# atx_power_control.net
KiCad netlist of a schematic drawn in EAGLE
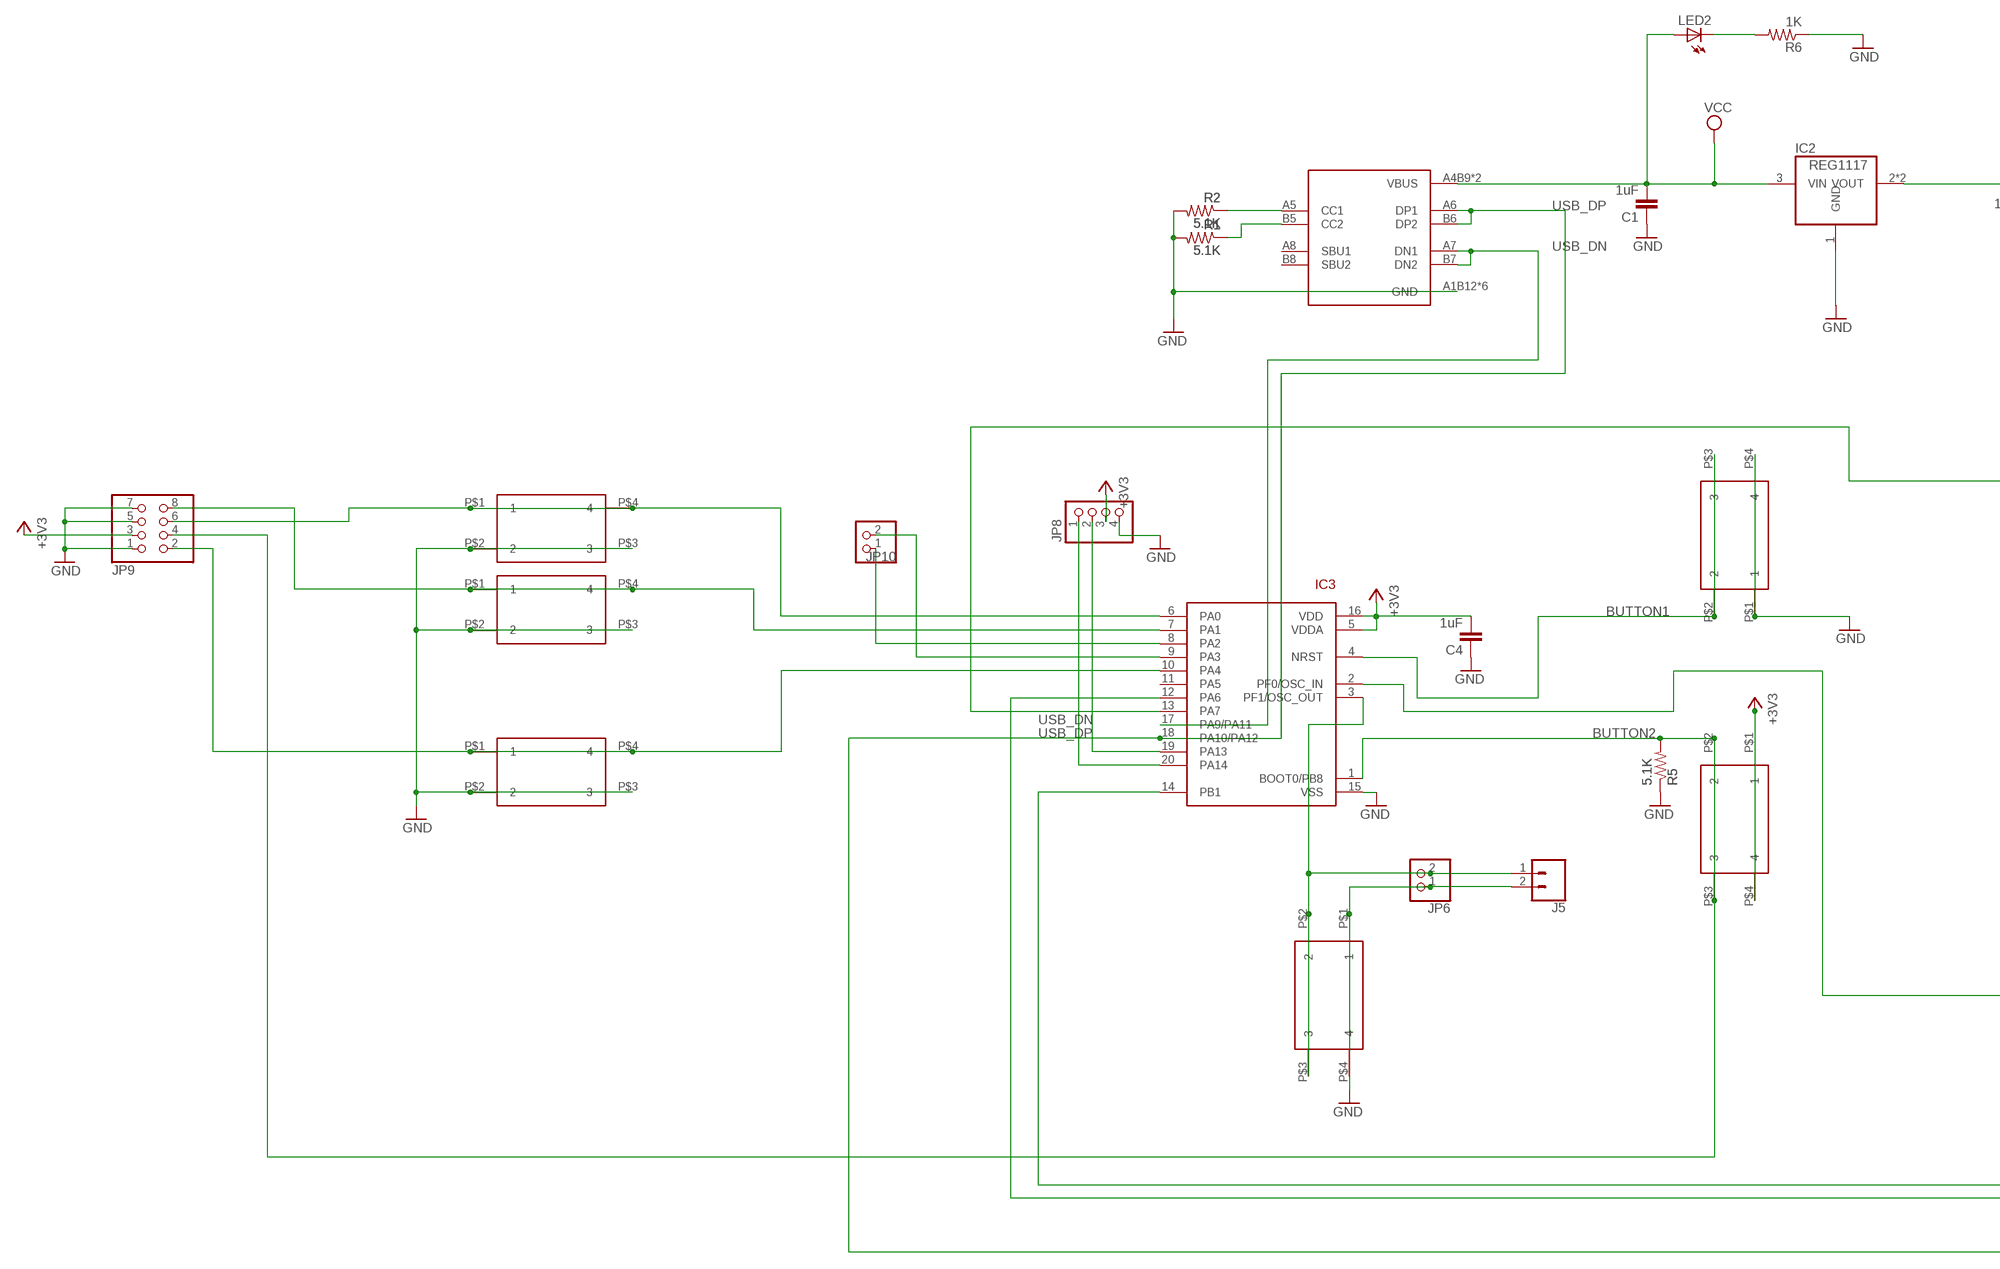
[diagram p0: schematic, sheet 1, part 1 of 2]
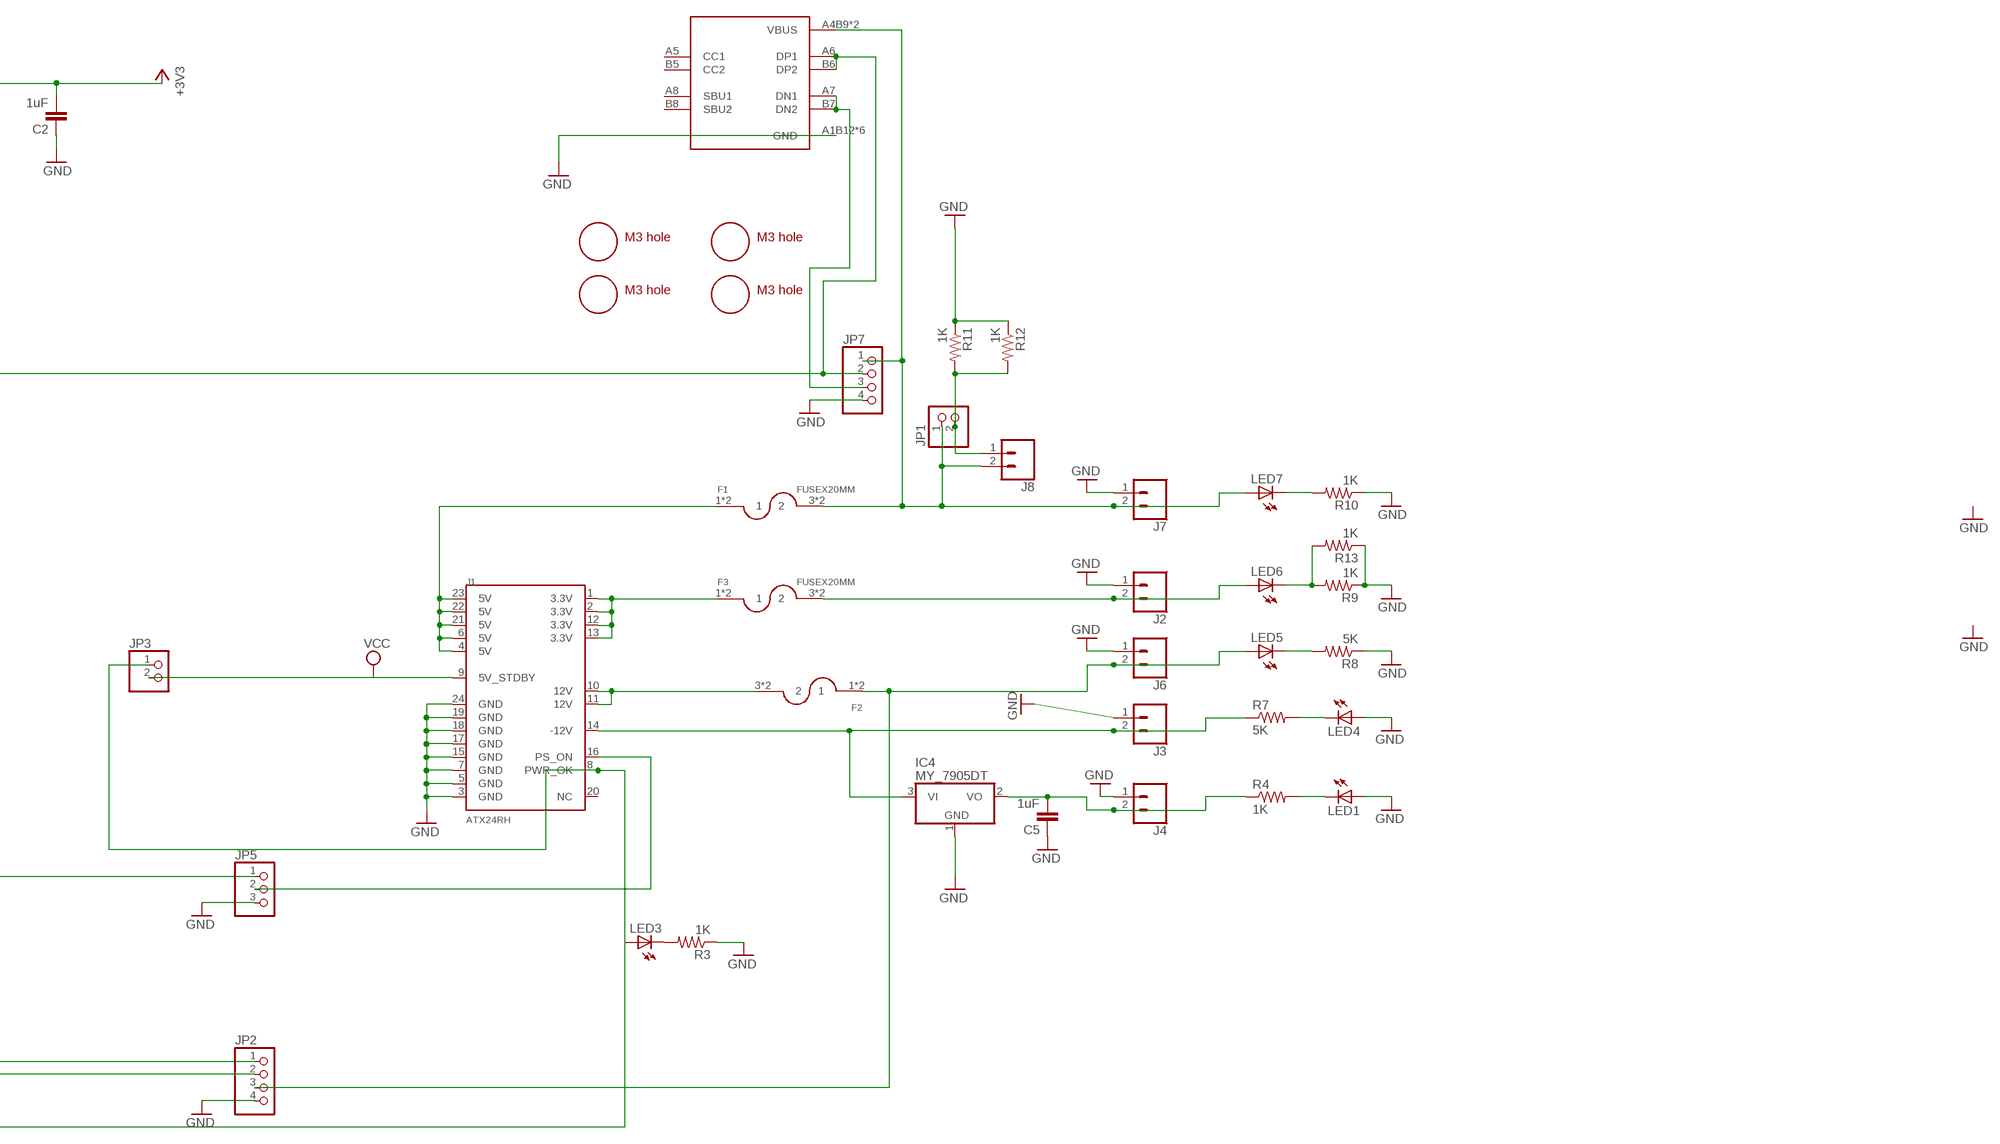
[diagram p1: schematic, sheet 1, part 2 of 2]

(export (version "E")
  (design (tool "Eeschema 10.0.6"))
  (components
    (comp (ref "C1")
      (value "1uF")
      (footprint "eagle-import:0805@1")
      (libsource (lib "eagle-import") (part "CAP0805"))
    )
    (comp (ref "C2")
      (value "1uF")
      (footprint "eagle-import:0805@1")
      (libsource (lib "eagle-import") (part "CAP0805"))
    )
    (comp (ref "C4")
      (value "1uF")
      (footprint "eagle-import:0805@1")
      (libsource (lib "eagle-import") (part "CAP0805"))
    )
    (comp (ref "C5")
      (value "1uF")
      (footprint "eagle-import:0805@1")
      (libsource (lib "eagle-import") (part "CAP0805"))
    )
    (comp (ref "F1")
      (value "FUSEX20MM")
      (footprint "eagle-import:FUSE_5MM")
      (libsource (lib "eagle-import") (part "FUSEX20MM"))
    )
    (comp (ref "F2")
      (value "FUSEX20MM")
      (footprint "eagle-import:FUSE_5MM")
      (libsource (lib "eagle-import") (part "FUSEX20MM"))
    )
    (comp (ref "F3")
      (value "FUSEX20MM")
      (footprint "eagle-import:FUSE_5MM")
      (libsource (lib "eagle-import") (part "FUSEX20MM"))
    )
    (comp (ref "IC2")
      (value "REG1117")
      (footprint "eagle-import:SOT223")
      (libsource (lib "eagle-import") (part "REG1117"))
    )
    (comp (ref "IC3")
      (value "STM32F042F4")
      (footprint "eagle-import:TSSOP20")
      (libsource (lib "eagle-import") (part "STM32F042F4"))
    )
    (comp (ref "IC4")
      (value "MY_7905DT")
      (footprint "eagle-import:ADAFRUIT_TO252")
      (libsource (lib "eagle-import") (part "MY_7905DT"))
    )
    (comp (ref "J1")
      (value "ATX24RH")
      (footprint "eagle-import:ATX24_RIGHT_ANGLE")
      (libsource (lib "eagle-import") (part "ATX24RH"))
    )
    (comp (ref "J2")
      (value "CONN_023.5MM")
      (footprint "eagle-import:SCREWTERMINAL-3.5MM-2")
      (libsource (lib "eagle-import") (part "CONN_023.5MM"))
    )
    (comp (ref "J3")
      (value "CONN_023.5MM")
      (footprint "eagle-import:SCREWTERMINAL-3.5MM-2")
      (libsource (lib "eagle-import") (part "CONN_023.5MM"))
    )
    (comp (ref "J4")
      (value "CONN_023.5MM")
      (footprint "eagle-import:SCREWTERMINAL-3.5MM-2")
      (libsource (lib "eagle-import") (part "CONN_023.5MM"))
    )
    (comp (ref "J5")
      (value "CONN_023.5MM")
      (footprint "eagle-import:SCREWTERMINAL-3.5MM-2")
      (libsource (lib "eagle-import") (part "CONN_023.5MM"))
    )
    (comp (ref "J6")
      (value "CONN_023.5MM")
      (footprint "eagle-import:SCREWTERMINAL-3.5MM-2")
      (libsource (lib "eagle-import") (part "CONN_023.5MM"))
    )
    (comp (ref "J7")
      (value "CONN_023.5MM-NO_SILK")
      (footprint "eagle-import:SCREWTERMINAL-3.5MM-2-NS")
      (libsource (lib "eagle-import") (part "CONN_023.5MM-NO_SILK"))
    )
    (comp (ref "J8")
      (value "CONN_023.5MM")
      (footprint "eagle-import:SCREWTERMINAL-3.5MM-2")
      (libsource (lib "eagle-import") (part "CONN_023.5MM"))
    )
    (comp (ref "JP1")
      (value "PINHD-1X2")
      (footprint "eagle-import:1X02")
      (libsource (lib "eagle-import") (part "PINHD-1X2"))
    )
    (comp (ref "JP2")
      (value "PINHD-1X4")
      (footprint "eagle-import:1X04")
      (libsource (lib "eagle-import") (part "PINHD-1X4"))
    )
    (comp (ref "JP3")
      (value "PINHD-1X2")
      (footprint "eagle-import:1X02")
      (libsource (lib "eagle-import") (part "PINHD-1X2"))
    )
    (comp (ref "JP5")
      (value "PINHD-1X3")
      (footprint "eagle-import:1X03")
      (libsource (lib "eagle-import") (part "PINHD-1X3"))
    )
    (comp (ref "JP6")
      (value "PINHD-1X2")
      (footprint "eagle-import:1X02")
      (libsource (lib "eagle-import") (part "PINHD-1X2"))
    )
    (comp (ref "JP7")
      (value "PINHD-1X4")
      (footprint "eagle-import:1X04")
      (libsource (lib "eagle-import") (part "PINHD-1X4"))
    )
    (comp (ref "JP8")
      (value "PINHD-1X4")
      (footprint "eagle-import:1X04")
      (libsource (lib "eagle-import") (part "PINHD-1X4"))
    )
    (comp (ref "JP9")
      (value "PINHD-2X4")
      (footprint "eagle-import:2X04")
      (libsource (lib "eagle-import") (part "PINHD-2X4"))
    )
    (comp (ref "JP10")
      (value "PINHD-1X2")
      (footprint "eagle-import:1X02")
      (libsource (lib "eagle-import") (part "PINHD-1X2"))
    )
    (comp (ref "LED1")
      (value "LEDCHIP-LED0805")
      (footprint "eagle-import:CHIP-LED0805")
      (libsource (lib "eagle-import") (part "LEDCHIP-LED0805"))
    )
    (comp (ref "LED2")
      (value "LEDCHIP-LED0805")
      (footprint "eagle-import:CHIP-LED0805")
      (libsource (lib "eagle-import") (part "LEDCHIP-LED0805"))
    )
    (comp (ref "LED3")
      (value "LEDCHIP-LED0805")
      (footprint "eagle-import:CHIP-LED0805")
      (libsource (lib "eagle-import") (part "LEDCHIP-LED0805"))
    )
    (comp (ref "LED4")
      (value "LEDCHIP-LED0805")
      (footprint "eagle-import:CHIP-LED0805")
      (libsource (lib "eagle-import") (part "LEDCHIP-LED0805"))
    )
    (comp (ref "LED5")
      (value "LEDCHIP-LED0805")
      (footprint "eagle-import:CHIP-LED0805")
      (libsource (lib "eagle-import") (part "LEDCHIP-LED0805"))
    )
    (comp (ref "LED6")
      (value "LEDCHIP-LED0805")
      (footprint "eagle-import:CHIP-LED0805")
      (libsource (lib "eagle-import") (part "LEDCHIP-LED0805"))
    )
    (comp (ref "LED7")
      (value "LEDCHIP-LED0805")
      (footprint "eagle-import:CHIP-LED0805")
      (libsource (lib "eagle-import") (part "LEDCHIP-LED0805"))
    )
    (comp (ref "R1")
      (value "5.1K")
      (footprint "eagle-import:0805")
      (libsource (lib "eagle-import") (part "joyAnalog_RESISTOR0805-RES"))
    )
    (comp (ref "R2")
      (value "5.1K")
      (footprint "eagle-import:0805")
      (libsource (lib "eagle-import") (part "joyAnalog_RESISTOR0805-RES"))
    )
    (comp (ref "R3")
      (value "1K")
      (footprint "eagle-import:0805")
      (libsource (lib "eagle-import") (part "RESISTOR0805-RES"))
    )
    (comp (ref "R4")
      (value "1K")
      (footprint "eagle-import:0805")
      (libsource (lib "eagle-import") (part "RESISTOR0805-RES"))
    )
    (comp (ref "R5")
      (value "5.1K")
      (footprint "eagle-import:0805")
      (libsource (lib "eagle-import") (part "joyAnalog_RESISTOR0805-RES"))
    )
    (comp (ref "R6")
      (value "1K")
      (footprint "eagle-import:0805")
      (libsource (lib "eagle-import") (part "RESISTOR0805-RES"))
    )
    (comp (ref "R7")
      (value "5K")
      (footprint "eagle-import:0805")
      (libsource (lib "eagle-import") (part "RESISTOR0805-RES"))
    )
    (comp (ref "R8")
      (value "5K")
      (footprint "eagle-import:0805")
      (libsource (lib "eagle-import") (part "RESISTOR0805-RES"))
    )
    (comp (ref "R9")
      (value "1K")
      (footprint "eagle-import:0805")
      (libsource (lib "eagle-import") (part "RESISTOR0805-RES"))
    )
    (comp (ref "R10")
      (value "1K")
      (footprint "eagle-import:0805")
      (libsource (lib "eagle-import") (part "RESISTOR0805-RES"))
    )
    (comp (ref "R11")
      (value "1K")
      (footprint "eagle-import:0805")
      (libsource (lib "eagle-import") (part "RESISTOR0805-RES"))
    )
    (comp (ref "R12")
      (value "1K")
      (footprint "eagle-import:0805")
      (libsource (lib "eagle-import") (part "RESISTOR0805-RES"))
    )
    (comp (ref "R13")
      (value "1K")
      (footprint "eagle-import:0805")
      (libsource (lib "eagle-import") (part "RESISTOR0805-RES"))
    )
    (comp (ref "SW1")
      (value "324_SW")
      (footprint "eagle-import:342_SWICH_FOOT")
      (libsource (lib "eagle-import") (part "324_SW"))
    )
    (comp (ref "SW2")
      (value "324_SW")
      (footprint "eagle-import:342_SWICH_FOOT")
      (libsource (lib "eagle-import") (part "324_SW"))
    )
    (comp (ref "SW3")
      (value "324_SW")
      (footprint "eagle-import:342_SWICH_FOOT")
      (libsource (lib "eagle-import") (part "324_SW"))
    )
    (comp (ref "SW4")
      (value "324_SW")
      (footprint "eagle-import:342_SWICH_FOOT")
      (libsource (lib "eagle-import") (part "324_SW"))
    )
    (comp (ref "SW5")
      (value "324_SW")
      (footprint "eagle-import:342_SWICH_FOOT")
      (libsource (lib "eagle-import") (part "324_SW"))
    )
    (comp (ref "SW7")
      (value "324_SW")
      (footprint "eagle-import:342_SWICH_FOOT")
      (libsource (lib "eagle-import") (part "324_SW"))
    )
    (comp (ref "U$1")
      (value "M3_MOUNTING_HOLE")
      (footprint "eagle-import:M3_MOUNTING_HOLE_PACK")
      (libsource (lib "eagle-import") (part "M3_MOUNTING_HOLE"))
    )
    (comp (ref "U$2")
      (value "M3_MOUNTING_HOLE")
      (footprint "eagle-import:M3_MOUNTING_HOLE_PACK")
      (libsource (lib "eagle-import") (part "M3_MOUNTING_HOLE"))
    )
    (comp (ref "U$3")
      (value "M3_MOUNTING_HOLE")
      (footprint "eagle-import:M3_MOUNTING_HOLE_PACK")
      (libsource (lib "eagle-import") (part "M3_MOUNTING_HOLE"))
    )
    (comp (ref "U$10")
      (value "M3_MOUNTING_HOLE")
      (footprint "eagle-import:M3_MOUNTING_HOLE_PACK")
      (libsource (lib "eagle-import") (part "M3_MOUNTING_HOLE"))
    )
    (comp (ref "U1")
      (value "USBC_16P")
      (footprint "eagle-import:USBC_16P_FOOT")
      (libsource (lib "eagle-import") (part "USBC_16P"))
    )
    (comp (ref "U2")
      (value "USBC_16P")
      (footprint "eagle-import:USBC_16P_FOOT")
      (libsource (lib "eagle-import") (part "USBC_16P"))
    )
  )
  (nets
    (net (code "1") (name "+3V3") (class "Default")
      (node (ref "C2") (pin "2") (pinfunction "2_2") (pintype "passive"))
      (node (ref "C4") (pin "2") (pinfunction "2_2") (pintype "passive"))
      (node (ref "IC2") (pin "2") (pinfunction "VOUT_2") (pintype "output"))
      (node (ref "IC2") (pin "4") (pinfunction "VOUT_4") (pintype "output"))
      (node (ref "IC3") (pin "16") (pinfunction "VDD_16") (pintype "bidirectional"))
      (node (ref "IC3") (pin "5") (pinfunction "VDDA_5") (pintype "bidirectional"))
      (node (ref "JP8") (pin "3") (pinfunction "3_3") (pintype "passive"))
      (node (ref "JP9") (pin "3") (pinfunction "3_3") (pintype "passive"))
      (node (ref "SW4") (pin "P$1") (pinfunction "1_P$1") (pintype "bidirectional"))
      (node (ref "SW4") (pin "P$4") (pinfunction "4_P$4") (pintype "bidirectional"))
    )
    (net (code "2") (name "/BUTTON1") (class "Default")
      (node (ref "IC3") (pin "4") (pinfunction "NRST_4") (pintype "bidirectional"))
      (node (ref "SW3") (pin "P$2") (pinfunction "2_P$2") (pintype "bidirectional"))
      (node (ref "SW3") (pin "P$3") (pinfunction "3_P$3") (pintype "bidirectional"))
    )
    (net (code "3") (name "/BUTTON2") (class "Default")
      (node (ref "IC3") (pin "1") (pinfunction "BOOT0/PB8_1") (pintype "bidirectional"))
      (node (ref "JP9") (pin "4") (pinfunction "4_4") (pintype "passive"))
      (node (ref "R5") (pin "2") (pinfunction "2_2") (pintype "passive"))
      (node (ref "SW4") (pin "P$2") (pinfunction "2_P$2") (pintype "bidirectional"))
      (node (ref "SW4") (pin "P$3") (pinfunction "3_P$3") (pintype "bidirectional"))
    )
    (net (code "4") (name "/USB_DN") (class "Default")
      (node (ref "IC3") (pin "17") (pinfunction "PA9/PA11_17") (pintype "bidirectional"))
      (node (ref "U2") (pin "A7") (pinfunction "DN1_A7") (pintype "bidirectional"))
      (node (ref "U2") (pin "B7") (pinfunction "DN2_B7") (pintype "bidirectional"))
    )
    (net (code "5") (name "/USB_DP") (class "Default")
      (node (ref "IC3") (pin "18") (pinfunction "PA10/PA12_18") (pintype "bidirectional"))
      (node (ref "J1") (pin "8") (pinfunction "PWR_OK_8") (pintype "bidirectional"))
      (node (ref "JP3") (pin "1") (pinfunction "1_1") (pintype "passive"))
      (node (ref "LED3") (pin "A") (pinfunction "A_A") (pintype "passive"))
      (node (ref "U2") (pin "A6") (pinfunction "DP1_A6") (pintype "bidirectional"))
      (node (ref "U2") (pin "B6") (pinfunction "DP2_B6") (pintype "bidirectional"))
    )
    (net (code "6") (name "GND") (class "Default")
      (node (ref "C1") (pin "1") (pinfunction "1_1") (pintype "passive"))
      (node (ref "C2") (pin "1") (pinfunction "1_1") (pintype "passive"))
      (node (ref "C4") (pin "1") (pinfunction "1_1") (pintype "passive"))
      (node (ref "C5") (pin "1") (pinfunction "1_1") (pintype "passive"))
      (node (ref "IC2") (pin "1") (pinfunction "GND_1") (pintype "power_in"))
      (node (ref "IC3") (pin "15") (pinfunction "VSS_15") (pintype "bidirectional"))
      (node (ref "IC4") (pin "1") (pinfunction "GND_1") (pintype "passive"))
      (node (ref "J1") (pin "15") (pinfunction "GND_15") (pintype "bidirectional"))
      (node (ref "J1") (pin "17") (pinfunction "GND_17") (pintype "bidirectional"))
      (node (ref "J1") (pin "18") (pinfunction "GND_18") (pintype "bidirectional"))
      (node (ref "J1") (pin "19") (pinfunction "GND_19") (pintype "bidirectional"))
      (node (ref "J1") (pin "24") (pinfunction "GND_24") (pintype "bidirectional"))
      (node (ref "J1") (pin "3") (pinfunction "GND_3") (pintype "bidirectional"))
      (node (ref "J1") (pin "5") (pinfunction "GND_5") (pintype "bidirectional"))
      (node (ref "J1") (pin "7") (pinfunction "GND_7") (pintype "bidirectional"))
      (node (ref "J2") (pin "1") (pinfunction "1_1") (pintype "passive"))
      (node (ref "J3") (pin "1") (pinfunction "1_1") (pintype "passive"))
      (node (ref "J4") (pin "1") (pinfunction "1_1") (pintype "passive"))
      (node (ref "J5") (pin "2") (pinfunction "2_2") (pintype "passive"))
      (node (ref "J6") (pin "1") (pinfunction "1_1") (pintype "passive"))
      (node (ref "J7") (pin "1") (pinfunction "1_1") (pintype "passive"))
      (node (ref "JP2") (pin "4") (pinfunction "4_4") (pintype "passive"))
      (node (ref "JP5") (pin "3") (pinfunction "3_3") (pintype "passive"))
      (node (ref "JP6") (pin "1") (pinfunction "1_1") (pintype "passive"))
      (node (ref "JP7") (pin "4") (pinfunction "4_4") (pintype "passive"))
      (node (ref "JP8") (pin "4") (pinfunction "4_4") (pintype "passive"))
      (node (ref "JP9") (pin "1") (pinfunction "1_1") (pintype "passive"))
      (node (ref "JP9") (pin "5") (pinfunction "5_5") (pintype "passive"))
      (node (ref "JP9") (pin "7") (pinfunction "7_7") (pintype "passive"))
      (node (ref "LED1") (pin "A") (pinfunction "A_A") (pintype "passive"))
      (node (ref "LED4") (pin "A") (pinfunction "A_A") (pintype "passive"))
      (node (ref "R1") (pin "2") (pinfunction "2_2") (pintype "passive"))
      (node (ref "R10") (pin "1") (pinfunction "1_1") (pintype "passive"))
      (node (ref "R11") (pin "1") (pinfunction "1_1") (pintype "passive"))
      (node (ref "R12") (pin "1") (pinfunction "1_1") (pintype "passive"))
      (node (ref "R13") (pin "1") (pinfunction "1_1") (pintype "passive"))
      (node (ref "R2") (pin "2") (pinfunction "2_2") (pintype "passive"))
      (node (ref "R3") (pin "1") (pinfunction "1_1") (pintype "passive"))
      (node (ref "R5") (pin "1") (pinfunction "1_1") (pintype "passive"))
      (node (ref "R6") (pin "1") (pinfunction "1_1") (pintype "passive"))
      (node (ref "R8") (pin "1") (pinfunction "1_1") (pintype "passive"))
      (node (ref "R9") (pin "1") (pinfunction "1_1") (pintype "passive"))
      (node (ref "SW1") (pin "P$1") (pinfunction "1_P$1") (pintype "bidirectional"))
      (node (ref "SW1") (pin "P$4") (pinfunction "4_P$4") (pintype "bidirectional"))
      (node (ref "SW2") (pin "P$2") (pinfunction "2_P$2") (pintype "bidirectional"))
      (node (ref "SW2") (pin "P$3") (pinfunction "3_P$3") (pintype "bidirectional"))
      (node (ref "SW3") (pin "P$1") (pinfunction "1_P$1") (pintype "bidirectional"))
      (node (ref "SW3") (pin "P$4") (pinfunction "4_P$4") (pintype "bidirectional"))
      (node (ref "SW5") (pin "P$2") (pinfunction "2_P$2") (pintype "bidirectional"))
      (node (ref "SW5") (pin "P$3") (pinfunction "3_P$3") (pintype "bidirectional"))
      (node (ref "SW7") (pin "P$2") (pinfunction "2_P$2") (pintype "bidirectional"))
      (node (ref "SW7") (pin "P$3") (pinfunction "3_P$3") (pintype "bidirectional"))
      (node (ref "U1") (pin "A1B12") (pinfunction "GND_A1B12") (pintype "bidirectional"))
      (node (ref "U1") (pin "B11A12") (pinfunction "GND_B11A12") (pintype "bidirectional"))
      (node (ref "U1") (pin "P$13") (pinfunction "GND_P$13") (pintype "bidirectional"))
      (node (ref "U1") (pin "P$14") (pinfunction "GND_P$14") (pintype "bidirectional"))
      (node (ref "U1") (pin "P$15") (pinfunction "GND_P$15") (pintype "bidirectional"))
      (node (ref "U1") (pin "P$16") (pinfunction "GND_P$16") (pintype "bidirectional"))
      (node (ref "U2") (pin "A1B12") (pinfunction "GND_A1B12") (pintype "bidirectional"))
      (node (ref "U2") (pin "B11A12") (pinfunction "GND_B11A12") (pintype "bidirectional"))
      (node (ref "U2") (pin "P$13") (pinfunction "GND_P$13") (pintype "bidirectional"))
      (node (ref "U2") (pin "P$14") (pinfunction "GND_P$14") (pintype "bidirectional"))
      (node (ref "U2") (pin "P$15") (pinfunction "GND_P$15") (pintype "bidirectional"))
      (node (ref "U2") (pin "P$16") (pinfunction "GND_P$16") (pintype "bidirectional"))
    )
    (net (code "7") (name "Net-(F1-1-Pad2)") (class "Default")
      (node (ref "F1") (pin "1") (pinfunction "1_1") (pintype "bidirectional"))
      (node (ref "F1") (pin "2") (pinfunction "1_2") (pintype "bidirectional"))
      (node (ref "J1") (pin "21") (pinfunction "5V_21") (pintype "bidirectional"))
      (node (ref "J1") (pin "22") (pinfunction "5V_22") (pintype "bidirectional"))
      (node (ref "J1") (pin "23") (pinfunction "5V_23") (pintype "bidirectional"))
      (node (ref "J1") (pin "4") (pinfunction "5V_4") (pintype "bidirectional"))
      (node (ref "J1") (pin "6") (pinfunction "5V_6") (pintype "bidirectional"))
    )
    (net (code "8") (name "Net-(F1-2-Pad3)") (class "Default")
      (node (ref "F1") (pin "3") (pinfunction "2_3") (pintype "bidirectional"))
      (node (ref "F1") (pin "4") (pinfunction "2_4") (pintype "bidirectional"))
      (node (ref "J7") (pin "2") (pinfunction "2_2") (pintype "passive"))
      (node (ref "J8") (pin "2") (pinfunction "2_2") (pintype "passive"))
      (node (ref "JP1") (pin "1") (pinfunction "1_1") (pintype "passive"))
      (node (ref "JP7") (pin "1") (pinfunction "1_1") (pintype "passive"))
      (node (ref "LED7") (pin "A") (pinfunction "A_A") (pintype "passive"))
      (node (ref "U1") (pin "A4B9") (pinfunction "VBUS_A4B9") (pintype "bidirectional"))
      (node (ref "U1") (pin "B4A9") (pinfunction "VBUS_B4A9") (pintype "bidirectional"))
    )
    (net (code "9") (name "Net-(F2-1-Pad2)") (class "Default")
      (node (ref "F2") (pin "1") (pinfunction "1_1") (pintype "bidirectional"))
      (node (ref "F2") (pin "2") (pinfunction "1_2") (pintype "bidirectional"))
      (node (ref "J6") (pin "2") (pinfunction "2_2") (pintype "passive"))
      (node (ref "JP2") (pin "3") (pinfunction "3_3") (pintype "passive"))
      (node (ref "LED5") (pin "A") (pinfunction "A_A") (pintype "passive"))
    )
    (net (code "10") (name "Net-(F2-2-Pad3)") (class "Default")
      (node (ref "F2") (pin "3") (pinfunction "2_3") (pintype "bidirectional"))
      (node (ref "F2") (pin "4") (pinfunction "2_4") (pintype "bidirectional"))
      (node (ref "J1") (pin "10") (pinfunction "12V_10") (pintype "bidirectional"))
      (node (ref "J1") (pin "11") (pinfunction "12V_11") (pintype "bidirectional"))
    )
    (net (code "11") (name "Net-(F3-1-Pad2)") (class "Default")
      (node (ref "F3") (pin "1") (pinfunction "1_1") (pintype "bidirectional"))
      (node (ref "F3") (pin "2") (pinfunction "1_2") (pintype "bidirectional"))
      (node (ref "J1") (pin "1") (pinfunction "3.3V_1") (pintype "bidirectional"))
      (node (ref "J1") (pin "12") (pinfunction "3.3V_12") (pintype "bidirectional"))
      (node (ref "J1") (pin "13") (pinfunction "3.3V_13") (pintype "bidirectional"))
      (node (ref "J1") (pin "2") (pinfunction "3.3V_2") (pintype "bidirectional"))
    )
    (net (code "12") (name "Net-(F3-2-Pad3)") (class "Default")
      (node (ref "F3") (pin "3") (pinfunction "2_3") (pintype "bidirectional"))
      (node (ref "F3") (pin "4") (pinfunction "2_4") (pintype "bidirectional"))
      (node (ref "J2") (pin "2") (pinfunction "2_2") (pintype "passive"))
      (node (ref "LED6") (pin "A") (pinfunction "A_A") (pintype "passive"))
    )
    (net (code "13") (name "Net-(IC3-PA0)") (class "Default")
      (node (ref "IC3") (pin "6") (pinfunction "PA0_6") (pintype "bidirectional"))
      (node (ref "JP9") (pin "6") (pinfunction "6_6") (pintype "passive"))
      (node (ref "SW2") (pin "P$1") (pinfunction "1_P$1") (pintype "bidirectional"))
      (node (ref "SW2") (pin "P$4") (pinfunction "4_P$4") (pintype "bidirectional"))
    )
    (net (code "14") (name "Net-(IC3-PA1)") (class "Default")
      (node (ref "IC3") (pin "7") (pinfunction "PA1_7") (pintype "bidirectional"))
      (node (ref "JP9") (pin "8") (pinfunction "8_8") (pintype "passive"))
      (node (ref "SW5") (pin "P$1") (pinfunction "1_P$1") (pintype "bidirectional"))
      (node (ref "SW5") (pin "P$4") (pinfunction "4_P$4") (pintype "bidirectional"))
    )
    (net (code "15") (name "Net-(IC3-PA2)") (class "Default")
      (node (ref "IC3") (pin "8") (pinfunction "PA2_8") (pintype "bidirectional"))
      (node (ref "JP10") (pin "1") (pinfunction "1_1") (pintype "passive"))
    )
    (net (code "16") (name "Net-(IC3-PA3)") (class "Default")
      (node (ref "IC3") (pin "9") (pinfunction "PA3_9") (pintype "bidirectional"))
      (node (ref "JP10") (pin "2") (pinfunction "2_2") (pintype "passive"))
    )
    (net (code "17") (name "Net-(IC3-PA4)") (class "Default")
      (node (ref "IC3") (pin "10") (pinfunction "PA4_10") (pintype "bidirectional"))
      (node (ref "JP9") (pin "2") (pinfunction "2_2") (pintype "passive"))
      (node (ref "SW7") (pin "P$1") (pinfunction "1_P$1") (pintype "bidirectional"))
      (node (ref "SW7") (pin "P$4") (pinfunction "4_P$4") (pintype "bidirectional"))
    )
    (net (code "18") (name "Net-(IC3-PA6)") (class "Default")
      (node (ref "IC3") (pin "12") (pinfunction "PA6_12") (pintype "bidirectional"))
      (node (ref "JP2") (pin "2") (pinfunction "2_2") (pintype "passive"))
    )
    (net (code "19") (name "Net-(IC3-PA7)") (class "Default")
      (node (ref "IC3") (pin "13") (pinfunction "PA7_13") (pintype "bidirectional"))
      (node (ref "JP7") (pin "2") (pinfunction "2_2") (pintype "passive"))
      (node (ref "U1") (pin "A6") (pinfunction "DP1_A6") (pintype "bidirectional"))
      (node (ref "U1") (pin "B6") (pinfunction "DP2_B6") (pintype "bidirectional"))
    )
    (net (code "20") (name "Net-(IC3-PA13)") (class "Default")
      (node (ref "IC3") (pin "19") (pinfunction "PA13_19") (pintype "bidirectional"))
      (node (ref "JP8") (pin "2") (pinfunction "2_2") (pintype "passive"))
    )
    (net (code "21") (name "Net-(IC3-PA14)") (class "Default")
      (node (ref "IC3") (pin "20") (pinfunction "PA14_20") (pintype "bidirectional"))
      (node (ref "JP8") (pin "1") (pinfunction "1_1") (pintype "passive"))
    )
    (net (code "22") (name "Net-(IC3-PB1)") (class "Default")
      (node (ref "IC3") (pin "14") (pinfunction "PB1_14") (pintype "bidirectional"))
      (node (ref "JP2") (pin "1") (pinfunction "1_1") (pintype "passive"))
    )
    (net (code "23") (name "Net-(IC3-PF0{slash}OSC_IN)") (class "Default")
      (node (ref "IC3") (pin "2") (pinfunction "PF0/OSC_IN_2") (pintype "bidirectional"))
      (node (ref "JP5") (pin "1") (pinfunction "1_1") (pintype "passive"))
    )
    (net (code "24") (name "Net-(IC3-PF1{slash}OSC_OUT)") (class "Default")
      (node (ref "IC3") (pin "3") (pinfunction "PF1/OSC_OUT_3") (pintype "bidirectional"))
      (node (ref "J5") (pin "1") (pinfunction "1_1") (pintype "passive"))
      (node (ref "JP6") (pin "2") (pinfunction "2_2") (pintype "passive"))
      (node (ref "SW1") (pin "P$2") (pinfunction "2_P$2") (pintype "bidirectional"))
      (node (ref "SW1") (pin "P$3") (pinfunction "3_P$3") (pintype "bidirectional"))
    )
    (net (code "25") (name "Net-(IC4-VI)") (class "Default")
      (node (ref "IC4") (pin "3") (pinfunction "VI_3") (pintype "input"))
      (node (ref "J1") (pin "14") (pinfunction "-12V_14") (pintype "bidirectional"))
      (node (ref "J3") (pin "2") (pinfunction "2_2") (pintype "passive"))
      (node (ref "R7") (pin "1") (pinfunction "1_1") (pintype "passive"))
    )
    (net (code "26") (name "Net-(IC4-VO)") (class "Default")
      (node (ref "C5") (pin "2") (pinfunction "2_2") (pintype "passive"))
      (node (ref "IC4") (pin "2") (pinfunction "VO_2") (pintype "passive"))
      (node (ref "J4") (pin "2") (pinfunction "2_2") (pintype "passive"))
      (node (ref "R4") (pin "1") (pinfunction "1_1") (pintype "passive"))
    )
    (net (code "27") (name "Net-(J1-PS_ON)") (class "Default")
      (node (ref "J1") (pin "16") (pinfunction "PS_ON_16") (pintype "bidirectional"))
      (node (ref "JP5") (pin "2") (pinfunction "2_2") (pintype "passive"))
    )
    (net (code "28") (name "Net-(J8-Pad1)") (class "Default")
      (node (ref "J8") (pin "1") (pinfunction "1_1") (pintype "passive"))
      (node (ref "JP1") (pin "2") (pinfunction "2_2") (pintype "passive"))
      (node (ref "R11") (pin "2") (pinfunction "2_2") (pintype "passive"))
      (node (ref "R12") (pin "2") (pinfunction "2_2") (pintype "passive"))
    )
    (net (code "29") (name "Net-(LED1-PadC)") (class "Default")
      (node (ref "LED1") (pin "C") (pinfunction "C_C") (pintype "passive"))
      (node (ref "R4") (pin "2") (pinfunction "2_2") (pintype "passive"))
    )
    (net (code "30") (name "Net-(LED2-PadC)") (class "Default")
      (node (ref "LED2") (pin "C") (pinfunction "C_C") (pintype "passive"))
      (node (ref "R6") (pin "2") (pinfunction "2_2") (pintype "passive"))
    )
    (net (code "31") (name "Net-(LED3-PadC)") (class "Default")
      (node (ref "LED3") (pin "C") (pinfunction "C_C") (pintype "passive"))
      (node (ref "R3") (pin "2") (pinfunction "2_2") (pintype "passive"))
    )
    (net (code "32") (name "Net-(LED4-PadC)") (class "Default")
      (node (ref "LED4") (pin "C") (pinfunction "C_C") (pintype "passive"))
      (node (ref "R7") (pin "2") (pinfunction "2_2") (pintype "passive"))
    )
    (net (code "33") (name "Net-(LED5-PadC)") (class "Default")
      (node (ref "LED5") (pin "C") (pinfunction "C_C") (pintype "passive"))
      (node (ref "R8") (pin "2") (pinfunction "2_2") (pintype "passive"))
    )
    (net (code "34") (name "Net-(LED6-PadC)") (class "Default")
      (node (ref "LED6") (pin "C") (pinfunction "C_C") (pintype "passive"))
      (node (ref "R13") (pin "2") (pinfunction "2_2") (pintype "passive"))
      (node (ref "R9") (pin "2") (pinfunction "2_2") (pintype "passive"))
    )
    (net (code "35") (name "Net-(LED7-PadC)") (class "Default")
      (node (ref "LED7") (pin "C") (pinfunction "C_C") (pintype "passive"))
      (node (ref "R10") (pin "2") (pinfunction "2_2") (pintype "passive"))
    )
    (net (code "36") (name "Net-(U1-DN1)") (class "Default")
      (node (ref "JP7") (pin "3") (pinfunction "3_3") (pintype "passive"))
      (node (ref "U1") (pin "A7") (pinfunction "DN1_A7") (pintype "bidirectional"))
      (node (ref "U1") (pin "B7") (pinfunction "DN2_B7") (pintype "bidirectional"))
    )
    (net (code "37") (name "Net-(U2-CC1)") (class "Default")
      (node (ref "R2") (pin "1") (pinfunction "1_1") (pintype "passive"))
      (node (ref "U2") (pin "A5") (pinfunction "CC1_A5") (pintype "bidirectional"))
    )
    (net (code "38") (name "Net-(U2-CC2)") (class "Default")
      (node (ref "R1") (pin "1") (pinfunction "1_1") (pintype "passive"))
      (node (ref "U2") (pin "B5") (pinfunction "CC2_B5") (pintype "bidirectional"))
    )
    (net (code "39") (name "VCC") (class "Default")
      (node (ref "C1") (pin "2") (pinfunction "2_2") (pintype "passive"))
      (node (ref "IC2") (pin "3") (pinfunction "VIN_3") (pintype "input"))
      (node (ref "J1") (pin "9") (pinfunction "5V_STDBY_9") (pintype "bidirectional"))
      (node (ref "JP3") (pin "2") (pinfunction "2_2") (pintype "passive"))
      (node (ref "LED2") (pin "A") (pinfunction "A_A") (pintype "passive"))
      (node (ref "U2") (pin "A4B9") (pinfunction "VBUS_A4B9") (pintype "bidirectional"))
      (node (ref "U2") (pin "B4A9") (pinfunction "VBUS_B4A9") (pintype "bidirectional"))
    )
    (net (code "40") (name "unconnected-(IC3-PA5-Pad11)") (class "Default")
      (node (ref "IC3") (pin "11") (pinfunction "PA5_11") (pintype "bidirectional"))
    )
    (net (code "41") (name "unconnected-(J1-NC-Pad20)") (class "Default")
      (node (ref "J1") (pin "20") (pinfunction "NC_20") (pintype "bidirectional"))
    )
    (net (code "42") (name "unconnected-(U1-CC1-PadA5)") (class "Default")
      (node (ref "U1") (pin "A5") (pinfunction "CC1_A5") (pintype "bidirectional"))
    )
    (net (code "43") (name "unconnected-(U1-CC2-PadB5)") (class "Default")
      (node (ref "U1") (pin "B5") (pinfunction "CC2_B5") (pintype "bidirectional"))
    )
    (net (code "44") (name "unconnected-(U1-SBU1-PadA8)") (class "Default")
      (node (ref "U1") (pin "A8") (pinfunction "SBU1_A8") (pintype "bidirectional"))
    )
    (net (code "45") (name "unconnected-(U1-SBU2-PadB8)") (class "Default")
      (node (ref "U1") (pin "B8") (pinfunction "SBU2_B8") (pintype "bidirectional"))
    )
    (net (code "46") (name "unconnected-(U2-SBU1-PadA8)") (class "Default")
      (node (ref "U2") (pin "A8") (pinfunction "SBU1_A8") (pintype "bidirectional"))
    )
    (net (code "47") (name "unconnected-(U2-SBU2-PadB8)") (class "Default")
      (node (ref "U2") (pin "B8") (pinfunction "SBU2_B8") (pintype "bidirectional"))
    )
  )
)
